# 4_Temperature_readings.net
KiCad netlist of a schematic drawn in Altium Designer
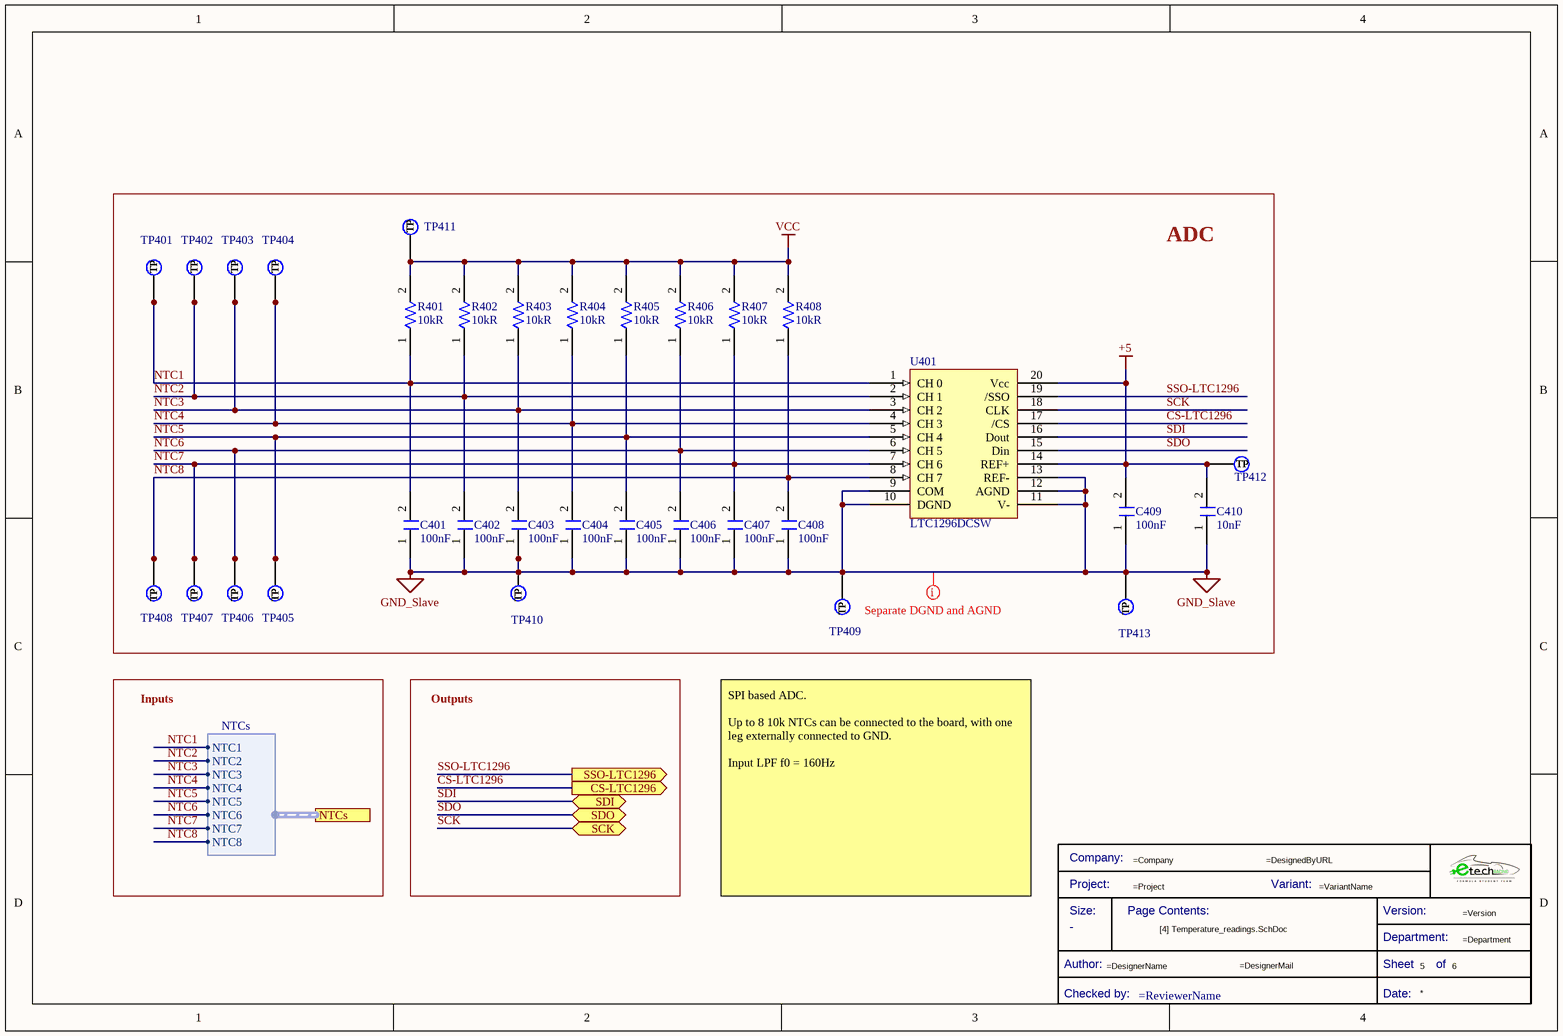
[diagram p0: [4] Temperature_readings.SchDoc]

(export (version "E")
  (design (tool "Eeschema 10.0.6"))
  (components
    (comp (ref "*")
      (value "Title Block_template")
      (description "Standard Title Block")
      (fields (field (name "SIZE") "-"))
      (libsource (lib "e-Tech_Racing") (part "Title Block_template"))
    )
    (comp (ref "C401")
      (value "885012207098")
      (footprint "C0805FNPC-R")
      (description "Cap, 0.1ΜF, 50V, 10%, X7R, 0805")
      (fields
        (field (name "TOLERANCE") "10%")
        (field (name "CAPACITANCE") "100nF")
        (field (name ".CREATOR") "DR")
      )
      (libsource (lib "Passives") (part "C100n-50V-0805FNPC-X7R"))
    )
    (comp (ref "C402")
      (value "885012207098")
      (footprint "C0805FNPC-R")
      (description "Cap, 0.1ΜF, 50V, 10%, X7R, 0805")
      (fields
        (field (name "TOLERANCE") "10%")
        (field (name "CAPACITANCE") "100nF")
        (field (name ".CREATOR") "DR")
      )
      (libsource (lib "Passives") (part "C100n-50V-0805FNPC-X7R"))
    )
    (comp (ref "C403")
      (value "885012207098")
      (footprint "C0805FNPC-R")
      (description "Cap, 0.1ΜF, 50V, 10%, X7R, 0805")
      (fields
        (field (name "TOLERANCE") "10%")
        (field (name "CAPACITANCE") "100nF")
        (field (name ".CREATOR") "DR")
      )
      (libsource (lib "Passives") (part "C100n-50V-0805FNPC-X7R"))
    )
    (comp (ref "C404")
      (value "885012207098")
      (footprint "C0805FNPC-R")
      (description "Cap, 0.1ΜF, 50V, 10%, X7R, 0805")
      (fields
        (field (name "TOLERANCE") "10%")
        (field (name "CAPACITANCE") "100nF")
        (field (name ".CREATOR") "DR")
      )
      (libsource (lib "Passives") (part "C100n-50V-0805FNPC-X7R"))
    )
    (comp (ref "C405")
      (value "885012207098")
      (footprint "C0805FNPC-R")
      (description "Cap, 0.1ΜF, 50V, 10%, X7R, 0805")
      (fields
        (field (name "TOLERANCE") "10%")
        (field (name "CAPACITANCE") "100nF")
        (field (name ".CREATOR") "DR")
      )
      (libsource (lib "Passives") (part "C100n-50V-0805FNPC-X7R"))
    )
    (comp (ref "C406")
      (value "885012207098")
      (footprint "C0805FNPC-R")
      (description "Cap, 0.1ΜF, 50V, 10%, X7R, 0805")
      (fields
        (field (name "TOLERANCE") "10%")
        (field (name "CAPACITANCE") "100nF")
        (field (name ".CREATOR") "DR")
      )
      (libsource (lib "Passives") (part "C100n-50V-0805FNPC-X7R"))
    )
    (comp (ref "C407")
      (value "885012207098")
      (footprint "C0805FNPC-R")
      (description "Cap, 0.1ΜF, 50V, 10%, X7R, 0805")
      (fields
        (field (name "TOLERANCE") "10%")
        (field (name "CAPACITANCE") "100nF")
        (field (name ".CREATOR") "DR")
      )
      (libsource (lib "Passives") (part "C100n-50V-0805FNPC-X7R"))
    )
    (comp (ref "C408")
      (value "885012207098")
      (footprint "C0805FNPC-R")
      (description "Cap, 0.1ΜF, 50V, 10%, X7R, 0805")
      (fields
        (field (name "TOLERANCE") "10%")
        (field (name "CAPACITANCE") "100nF")
        (field (name ".CREATOR") "DR")
      )
      (libsource (lib "Passives") (part "C100n-50V-0805FNPC-X7R"))
    )
    (comp (ref "C409")
      (value "885012207098")
      (footprint "C0805FNPC-R")
      (description "Cap, 0.1ΜF, 50V, 10%, X7R, 0805")
      (fields
        (field (name "TOLERANCE") "10%")
        (field (name "CAPACITANCE") "100nF")
        (field (name ".CREATOR") "DR")
      )
      (libsource (lib "Passives") (part "C100n-50V-0805FNPC-X7R"))
    )
    (comp (ref "C410")
      (value "885012207092")
      (footprint "C0805FNPC-R")
      (description "Cap, 0.01ΜF, 50V, 10%, X7R, 0805")
      (fields
        (field (name "TOLERANCE") "10%")
        (field (name "CAPACITANCE") "10nF")
        (field (name ".CREATOR") "DR")
      )
      (libsource (lib "Passives") (part "C10n-50V-0805FNPC-X7R"))
    )
    (comp (ref "R401")
      (value "CR0805-JW-103ELF")
      (footprint "R0805FTK")
      (fields
        (field (name "TOLERANCE") "5%")
        (field (name "RESISTANCE") "10kR")
        (field (name ".CREATOR") "DR")
      )
      (libsource (lib "Passives") (part "R10k-0805FTK"))
    )
    (comp (ref "R402")
      (value "CR0805-JW-103ELF")
      (footprint "R0805FTK")
      (fields
        (field (name "TOLERANCE") "5%")
        (field (name "RESISTANCE") "10kR")
        (field (name ".CREATOR") "DR")
      )
      (libsource (lib "Passives") (part "R10k-0805FTK"))
    )
    (comp (ref "R403")
      (value "CR0805-JW-103ELF")
      (footprint "R0805FTK")
      (fields
        (field (name "TOLERANCE") "5%")
        (field (name "RESISTANCE") "10kR")
        (field (name ".CREATOR") "DR")
      )
      (libsource (lib "Passives") (part "R10k-0805FTK"))
    )
    (comp (ref "R404")
      (value "CR0805-JW-103ELF")
      (footprint "R0805FTK")
      (fields
        (field (name "TOLERANCE") "5%")
        (field (name "RESISTANCE") "10kR")
        (field (name ".CREATOR") "DR")
      )
      (libsource (lib "Passives") (part "R10k-0805FTK"))
    )
    (comp (ref "R405")
      (value "CR0805-JW-103ELF")
      (footprint "R0805FTK")
      (fields
        (field (name "TOLERANCE") "5%")
        (field (name "RESISTANCE") "10kR")
        (field (name ".CREATOR") "DR")
      )
      (libsource (lib "Passives") (part "R10k-0805FTK"))
    )
    (comp (ref "R406")
      (value "CR0805-JW-103ELF")
      (footprint "R0805FTK")
      (fields
        (field (name "TOLERANCE") "5%")
        (field (name "RESISTANCE") "10kR")
        (field (name ".CREATOR") "DR")
      )
      (libsource (lib "Passives") (part "R10k-0805FTK"))
    )
    (comp (ref "R407")
      (value "CR0805-JW-103ELF")
      (footprint "R0805FTK")
      (fields
        (field (name "TOLERANCE") "5%")
        (field (name "RESISTANCE") "10kR")
        (field (name ".CREATOR") "DR")
      )
      (libsource (lib "Passives") (part "R10k-0805FTK"))
    )
    (comp (ref "R408")
      (value "CR0805-JW-103ELF")
      (footprint "R0805FTK")
      (fields
        (field (name "TOLERANCE") "5%")
        (field (name "RESISTANCE") "10kR")
        (field (name ".CREATOR") "DR")
      )
      (libsource (lib "Passives") (part "R10k-0805FTK"))
    )
    (comp (ref "TP401")
      (value "TestPoint")
      (footprint "TestPoint")
      (description "Test Point 1x1 mm")
      (fields (field (name ".CREATOR") "GP") (field (name ".PCBCHECK") "GP") (field (name ".SCHCHECK") "GP"))
      (libsource (lib "e-Tech_Racing") (part "TestPoint"))
    )
    (comp (ref "TP402")
      (value "TestPoint")
      (footprint "TestPoint")
      (description "Test Point 1x1 mm")
      (fields (field (name ".CREATOR") "GP") (field (name ".PCBCHECK") "GP") (field (name ".SCHCHECK") "GP"))
      (libsource (lib "e-Tech_Racing") (part "TestPoint"))
    )
    (comp (ref "TP403")
      (value "TestPoint")
      (footprint "TestPoint")
      (description "Test Point 1x1 mm")
      (fields (field (name ".CREATOR") "GP") (field (name ".PCBCHECK") "GP") (field (name ".SCHCHECK") "GP"))
      (libsource (lib "e-Tech_Racing") (part "TestPoint"))
    )
    (comp (ref "TP404")
      (value "TestPoint")
      (footprint "TestPoint")
      (description "Test Point 1x1 mm")
      (fields (field (name ".CREATOR") "GP") (field (name ".PCBCHECK") "GP") (field (name ".SCHCHECK") "GP"))
      (libsource (lib "e-Tech_Racing") (part "TestPoint"))
    )
    (comp (ref "TP405")
      (value "TestPoint")
      (footprint "TestPoint")
      (description "Test Point 1x1 mm")
      (fields (field (name ".CREATOR") "GP") (field (name ".PCBCHECK") "GP") (field (name ".SCHCHECK") "GP"))
      (libsource (lib "e-Tech_Racing") (part "TestPoint"))
    )
    (comp (ref "TP406")
      (value "TestPoint")
      (footprint "TestPoint")
      (description "Test Point 1x1 mm")
      (fields (field (name ".CREATOR") "GP") (field (name ".PCBCHECK") "GP") (field (name ".SCHCHECK") "GP"))
      (libsource (lib "e-Tech_Racing") (part "TestPoint"))
    )
    (comp (ref "TP407")
      (value "TestPoint")
      (footprint "TestPoint")
      (description "Test Point 1x1 mm")
      (fields (field (name ".CREATOR") "GP") (field (name ".PCBCHECK") "GP") (field (name ".SCHCHECK") "GP"))
      (libsource (lib "e-Tech_Racing") (part "TestPoint"))
    )
    (comp (ref "TP408")
      (value "TestPoint")
      (footprint "TestPoint")
      (description "Test Point 1x1 mm")
      (fields (field (name ".CREATOR") "GP") (field (name ".PCBCHECK") "GP") (field (name ".SCHCHECK") "GP"))
      (libsource (lib "e-Tech_Racing") (part "TestPoint"))
    )
    (comp (ref "TP409")
      (value "TestPoint")
      (footprint "TestPoint")
      (description "Test Point 1x1 mm")
      (fields (field (name ".CREATOR") "GP") (field (name ".PCBCHECK") "GP") (field (name ".SCHCHECK") "GP"))
      (libsource (lib "e-Tech_Racing") (part "TestPoint"))
    )
    (comp (ref "TP410")
      (value "TestPoint")
      (footprint "TestPoint")
      (description "Test Point 1x1 mm")
      (fields (field (name ".CREATOR") "GP") (field (name ".PCBCHECK") "GP") (field (name ".SCHCHECK") "GP"))
      (libsource (lib "e-Tech_Racing") (part "TestPoint"))
    )
    (comp (ref "TP411")
      (value "TestPoint")
      (footprint "TestPoint")
      (description "Test Point 1x1 mm")
      (fields (field (name ".CREATOR") "GP") (field (name ".PCBCHECK") "GP") (field (name ".SCHCHECK") "GP"))
      (libsource (lib "e-Tech_Racing") (part "TestPoint"))
    )
    (comp (ref "TP412")
      (value "TestPoint")
      (footprint "TestPoint")
      (description "Test Point 1x1 mm")
      (fields (field (name ".CREATOR") "GP") (field (name ".PCBCHECK") "GP") (field (name ".SCHCHECK") "GP"))
      (libsource (lib "e-Tech_Racing") (part "TestPoint"))
    )
    (comp (ref "TP413")
      (value "TestPoint")
      (footprint "TestPoint")
      (description "Test Point 1x1 mm")
      (fields (field (name ".CREATOR") "GP") (field (name ".PCBCHECK") "GP") (field (name ".SCHCHECK") "GP"))
      (libsource (lib "e-Tech_Racing") (part "TestPoint"))
    )
    (comp (ref "U401")
      (value "LTC1296")
      (footprint "ADC_LTC1296")
      (description "8-Channel Single ADC SAR 46.5ksps 12-bit Serial 20-Pin SOIC W")
      (fields (field (name "MANUFACTURER PART NUMBER 1") "LTC1296DCSW") (field (name ".CREATOR") "DR"))
      (libsource (lib "Integrated circuits") (part "ADC-LTC1296"))
    )
  )
  (nets
    (net (code "2") (name "+5") (class "Default")
      (node (ref "C409") (pin "2") (pinfunction "2_2") (pintype "passive"))
      (node (ref "C410") (pin "2") (pinfunction "2_2") (pintype "passive"))
      (node (ref "TP412") (pin "1") (pinfunction "TP_1") (pintype "passive"))
      (node (ref "U401") (pin "14") (pinfunction "REF+_14") (pintype "passive"))
      (node (ref "U401") (pin "20") (pinfunction "Vcc_20") (pintype "passive"))
    )
    (net (code "3") (name "/CS-LTC1296") (class "Default")
      (node (ref "U401") (pin "17") (pinfunction "/CS_17") (pintype "passive"))
    )
    (net (code "4") (name "/NTC1") (class "Default")
      (node (ref "C401") (pin "2") (pinfunction "2_2") (pintype "passive"))
      (node (ref "R401") (pin "1") (pinfunction "1_1") (pintype "passive"))
      (node (ref "TP401") (pin "1") (pinfunction "TP_1") (pintype "passive"))
      (node (ref "U401") (pin "1") (pinfunction "CH_0_1") (pintype "input"))
    )
    (net (code "5") (name "/NTC2") (class "Default")
      (node (ref "C402") (pin "2") (pinfunction "2_2") (pintype "passive"))
      (node (ref "R402") (pin "1") (pinfunction "1_1") (pintype "passive"))
      (node (ref "TP402") (pin "1") (pinfunction "TP_1") (pintype "passive"))
      (node (ref "U401") (pin "2") (pinfunction "CH_1_2") (pintype "input"))
    )
    (net (code "6") (name "/NTC3") (class "Default")
      (node (ref "C403") (pin "2") (pinfunction "2_2") (pintype "passive"))
      (node (ref "R403") (pin "1") (pinfunction "1_1") (pintype "passive"))
      (node (ref "TP403") (pin "1") (pinfunction "TP_1") (pintype "passive"))
      (node (ref "U401") (pin "3") (pinfunction "CH_2_3") (pintype "input"))
    )
    (net (code "7") (name "/NTC4") (class "Default")
      (node (ref "C404") (pin "2") (pinfunction "2_2") (pintype "passive"))
      (node (ref "R404") (pin "1") (pinfunction "1_1") (pintype "passive"))
      (node (ref "TP404") (pin "1") (pinfunction "TP_1") (pintype "passive"))
      (node (ref "U401") (pin "4") (pinfunction "CH_3_4") (pintype "input"))
    )
    (net (code "8") (name "/NTC5") (class "Default")
      (node (ref "C405") (pin "2") (pinfunction "2_2") (pintype "passive"))
      (node (ref "R405") (pin "1") (pinfunction "1_1") (pintype "passive"))
      (node (ref "TP405") (pin "1") (pinfunction "TP_1") (pintype "passive"))
      (node (ref "U401") (pin "5") (pinfunction "CH_4_5") (pintype "input"))
    )
    (net (code "9") (name "/NTC6") (class "Default")
      (node (ref "C406") (pin "2") (pinfunction "2_2") (pintype "passive"))
      (node (ref "R406") (pin "1") (pinfunction "1_1") (pintype "passive"))
      (node (ref "TP406") (pin "1") (pinfunction "TP_1") (pintype "passive"))
      (node (ref "U401") (pin "6") (pinfunction "CH_5_6") (pintype "input"))
    )
    (net (code "10") (name "/NTC7") (class "Default")
      (node (ref "C407") (pin "2") (pinfunction "2_2") (pintype "passive"))
      (node (ref "R407") (pin "1") (pinfunction "1_1") (pintype "passive"))
      (node (ref "TP407") (pin "1") (pinfunction "TP_1") (pintype "passive"))
      (node (ref "U401") (pin "7") (pinfunction "CH_6_7") (pintype "input"))
    )
    (net (code "11") (name "/NTC8") (class "Default")
      (node (ref "C408") (pin "2") (pinfunction "2_2") (pintype "passive"))
      (node (ref "R408") (pin "1") (pinfunction "1_1") (pintype "passive"))
      (node (ref "TP408") (pin "1") (pinfunction "TP_1") (pintype "passive"))
      (node (ref "U401") (pin "8") (pinfunction "CH_7_8") (pintype "input"))
    )
    (net (code "12") (name "/SCK") (class "Default")
      (node (ref "U401") (pin "18") (pinfunction "CLK_18") (pintype "passive"))
    )
    (net (code "13") (name "/SDI") (class "Default")
      (node (ref "U401") (pin "16") (pinfunction "Dout_16") (pintype "passive"))
    )
    (net (code "14") (name "/SDO") (class "Default")
      (node (ref "U401") (pin "15") (pinfunction "Din_15") (pintype "passive"))
    )
    (net (code "15") (name "/SSO-LTC1296") (class "Default")
      (node (ref "U401") (pin "19") (pinfunction "/SSO_19") (pintype "passive"))
    )
    (net (code "17") (name "GND_Slave") (class "Default")
      (node (ref "C401") (pin "1") (pinfunction "1_1") (pintype "passive"))
      (node (ref "C402") (pin "1") (pinfunction "1_1") (pintype "passive"))
      (node (ref "C403") (pin "1") (pinfunction "1_1") (pintype "passive"))
      (node (ref "C404") (pin "1") (pinfunction "1_1") (pintype "passive"))
      (node (ref "C405") (pin "1") (pinfunction "1_1") (pintype "passive"))
      (node (ref "C406") (pin "1") (pinfunction "1_1") (pintype "passive"))
      (node (ref "C407") (pin "1") (pinfunction "1_1") (pintype "passive"))
      (node (ref "C408") (pin "1") (pinfunction "1_1") (pintype "passive"))
      (node (ref "C409") (pin "1") (pinfunction "1_1") (pintype "passive"))
      (node (ref "C410") (pin "1") (pinfunction "1_1") (pintype "passive"))
      (node (ref "TP409") (pin "1") (pinfunction "TP_1") (pintype "passive"))
      (node (ref "TP410") (pin "1") (pinfunction "TP_1") (pintype "passive"))
      (node (ref "TP413") (pin "1") (pinfunction "TP_1") (pintype "passive"))
      (node (ref "U401") (pin "10") (pinfunction "DGND_10") (pintype "passive"))
      (node (ref "U401") (pin "11") (pinfunction "V-_11") (pintype "passive"))
      (node (ref "U401") (pin "12") (pinfunction "AGND_12") (pintype "passive"))
      (node (ref "U401") (pin "13") (pinfunction "REF-_13") (pintype "passive"))
      (node (ref "U401") (pin "9") (pinfunction "COM_9") (pintype "passive"))
    )
    (net (code "18") (name "VCC") (class "Default")
      (node (ref "R401") (pin "2") (pinfunction "2_2") (pintype "passive"))
      (node (ref "R402") (pin "2") (pinfunction "2_2") (pintype "passive"))
      (node (ref "R403") (pin "2") (pinfunction "2_2") (pintype "passive"))
      (node (ref "R404") (pin "2") (pinfunction "2_2") (pintype "passive"))
      (node (ref "R405") (pin "2") (pinfunction "2_2") (pintype "passive"))
      (node (ref "R406") (pin "2") (pinfunction "2_2") (pintype "passive"))
      (node (ref "R407") (pin "2") (pinfunction "2_2") (pintype "passive"))
      (node (ref "R408") (pin "2") (pinfunction "2_2") (pintype "passive"))
      (node (ref "TP411") (pin "1") (pinfunction "TP_1") (pintype "passive"))
    )
  )
)
